# MRCS-MSS-Detector-Crossover.net
KiCad netlist of a schematic drawn in EAGLE
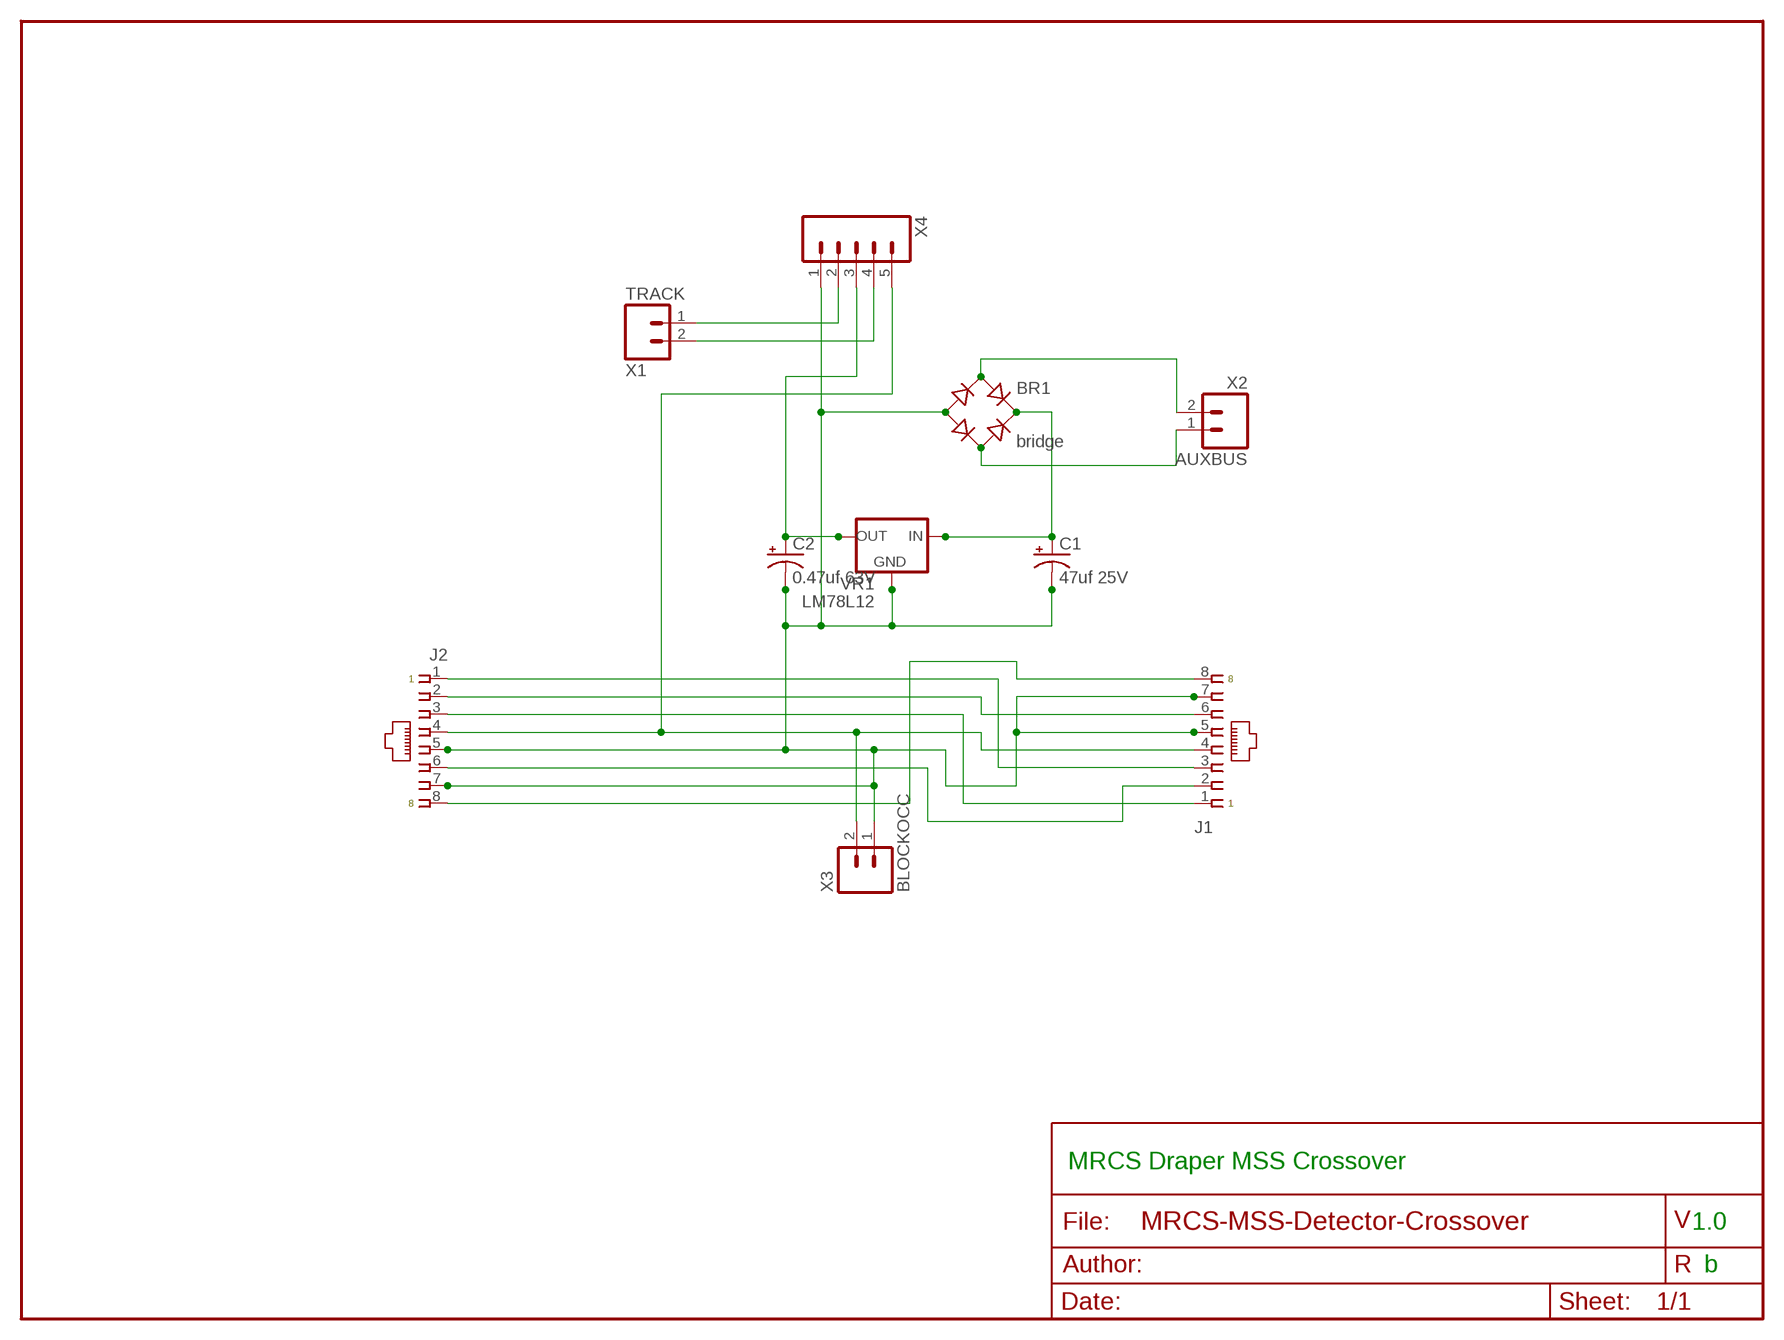
[diagram p0: schematic, sheet 1]

(export (version "E")
  (design (tool "Eeschema 10.0.6"))
  (components
    (comp (ref "BR1")
      (value "bridge")
      (footprint "eagle-import:RB1A")
      (libsource (lib "eagle-import") (part "DB?GRB1A"))
    )
    (comp (ref "C1")
      (value "47uf 25V")
      (footprint "eagle-import:E2.5-6")
      (libsource (lib "eagle-import") (part "CAP-POLPTH-2.5MM"))
    )
    (comp (ref "C2")
      (value "0.47uf 63V")
      (footprint "eagle-import:E2.5-6")
      (libsource (lib "eagle-import") (part "CAP-POLPTH-2.5MM"))
    )
    (comp (ref "J1")
      (value "CONNECTOR-RJ45-FRONT")
      (footprint "eagle-import:RJ45-NO-SHIELD")
      (libsource (lib "eagle-import") (part "CONNECTOR-RJ45-FRONT"))
    )
    (comp (ref "J2")
      (value "CONNECTOR-RJ45-FRONT")
      (footprint "eagle-import:RJ45-NO-SHIELD")
      (libsource (lib "eagle-import") (part "CONNECTOR-RJ45-FRONT"))
    )
    (comp (ref "VR1")
      (value "LM78L12")
      (footprint "eagle-import:TO-92")
      (libsource (lib "eagle-import") (part "VREG-?-TO-9212"))
    )
    (comp (ref "X1")
      (value "TRACK")
      (footprint "eagle-import:SCREWTERMINAL-5MM-2")
      (libsource (lib "eagle-import") (part "CONNECTOR-M025MM-LOCK"))
    )
    (comp (ref "X2")
      (value "AUXBUS")
      (footprint "eagle-import:SCREWTERMINAL-5MM-2")
      (libsource (lib "eagle-import") (part "CONNECTOR-M025MM-LOCK"))
    )
    (comp (ref "X3")
      (value "BLOCKOCC")
      (footprint "eagle-import:SCREWTERMINAL-5MM-2")
      (libsource (lib "eagle-import") (part "CONNECTOR-M025MM-LOCK"))
    )
    (comp (ref "X4")
      (value "CONNECTOR-M051.56")
      (footprint "eagle-import:KK-156-5")
      (libsource (lib "eagle-import") (part "CONNECTOR-M051.56"))
    )
  )
  (nets
    (net (code "1") (name "Net-(J1-Pad1)") (class "Default")
      (node (ref "J1") (pin "1") (pinfunction "1_1") (pintype "passive"))
      (node (ref "J2") (pin "3") (pinfunction "3_3") (pintype "passive"))
    )
    (net (code "2") (name "Net-(J1-Pad2)") (class "Default")
      (node (ref "J1") (pin "2") (pinfunction "2_2") (pintype "passive"))
      (node (ref "J2") (pin "6") (pinfunction "6_6") (pintype "passive"))
    )
    (net (code "3") (name "Net-(J1-Pad3)") (class "Default")
      (node (ref "J1") (pin "3") (pinfunction "3_3") (pintype "passive"))
      (node (ref "J2") (pin "1") (pinfunction "1_1") (pintype "passive"))
    )
    (net (code "4") (name "Net-(J1-Pad6)") (class "Default")
      (node (ref "J1") (pin "6") (pinfunction "6_6") (pintype "passive"))
      (node (ref "J2") (pin "2") (pinfunction "2_2") (pintype "passive"))
    )
    (net (code "5") (name "Net-(J1-Pad8)") (class "Default")
      (node (ref "J1") (pin "8") (pinfunction "8_8") (pintype "passive"))
      (node (ref "J2") (pin "8") (pinfunction "8_8") (pintype "passive"))
    )
    (net (code "6") (name "Net-(VR1-GND)") (class "Default")
      (node (ref "BR1") (pin "-") (pinfunction "-_-") (pintype "passive"))
      (node (ref "C1") (pin "-") (pinfunction "-_-") (pintype "passive"))
      (node (ref "C2") (pin "-") (pinfunction "-_-") (pintype "passive"))
      (node (ref "J1") (pin "5") (pinfunction "5_5") (pintype "passive"))
      (node (ref "J1") (pin "7") (pinfunction "7_7") (pintype "passive"))
      (node (ref "J2") (pin "5") (pinfunction "5_5") (pintype "passive"))
      (node (ref "J2") (pin "7") (pinfunction "7_7") (pintype "passive"))
      (node (ref "VR1") (pin "1") (pinfunction "GND_1") (pintype "input"))
      (node (ref "X3") (pin "1") (pinfunction "A_1") (pintype "passive"))
      (node (ref "X4") (pin "1") (pinfunction "1_1") (pintype "passive"))
    )
    (net (code "7") (name "Net-(VR1-IN)") (class "Default")
      (node (ref "BR1") (pin "+") (pinfunction "+_+") (pintype "passive"))
      (node (ref "C1") (pin "+") (pinfunction "+_+") (pintype "passive"))
      (node (ref "VR1") (pin "2") (pinfunction "IN_2") (pintype "input"))
    )
    (net (code "8") (name "Net-(VR1-OUT)") (class "Default")
      (node (ref "C2") (pin "+") (pinfunction "+_+") (pintype "passive"))
      (node (ref "VR1") (pin "3") (pinfunction "OUT_3") (pintype "output"))
      (node (ref "X4") (pin "3") (pinfunction "3_3") (pintype "passive"))
    )
    (net (code "9") (name "Net-(X1-A)") (class "Default")
      (node (ref "X1") (pin "1") (pinfunction "A_1") (pintype "passive"))
      (node (ref "X4") (pin "2") (pinfunction "2_2") (pintype "passive"))
    )
    (net (code "10") (name "Net-(X1-B)") (class "Default")
      (node (ref "X1") (pin "2") (pinfunction "B_2") (pintype "passive"))
      (node (ref "X4") (pin "4") (pinfunction "4_4") (pintype "passive"))
    )
    (net (code "11") (name "Net-(X2-A)") (class "Default")
      (node (ref "BR1") (pin "AC2") (pinfunction "AC2_AC2") (pintype "passive"))
      (node (ref "X2") (pin "1") (pinfunction "A_1") (pintype "passive"))
    )
    (net (code "12") (name "Net-(X2-B)") (class "Default")
      (node (ref "BR1") (pin "AC1") (pinfunction "AC1_AC1") (pintype "passive"))
      (node (ref "X2") (pin "2") (pinfunction "B_2") (pintype "passive"))
    )
    (net (code "13") (name "Net-(X3-B)") (class "Default")
      (node (ref "J1") (pin "4") (pinfunction "4_4") (pintype "passive"))
      (node (ref "J2") (pin "4") (pinfunction "4_4") (pintype "passive"))
      (node (ref "X3") (pin "2") (pinfunction "B_2") (pintype "passive"))
      (node (ref "X4") (pin "5") (pinfunction "5_5") (pintype "passive"))
    )
  )
)
